# Decode.net
KiCad netlist of a schematic drawn in Altium Designer
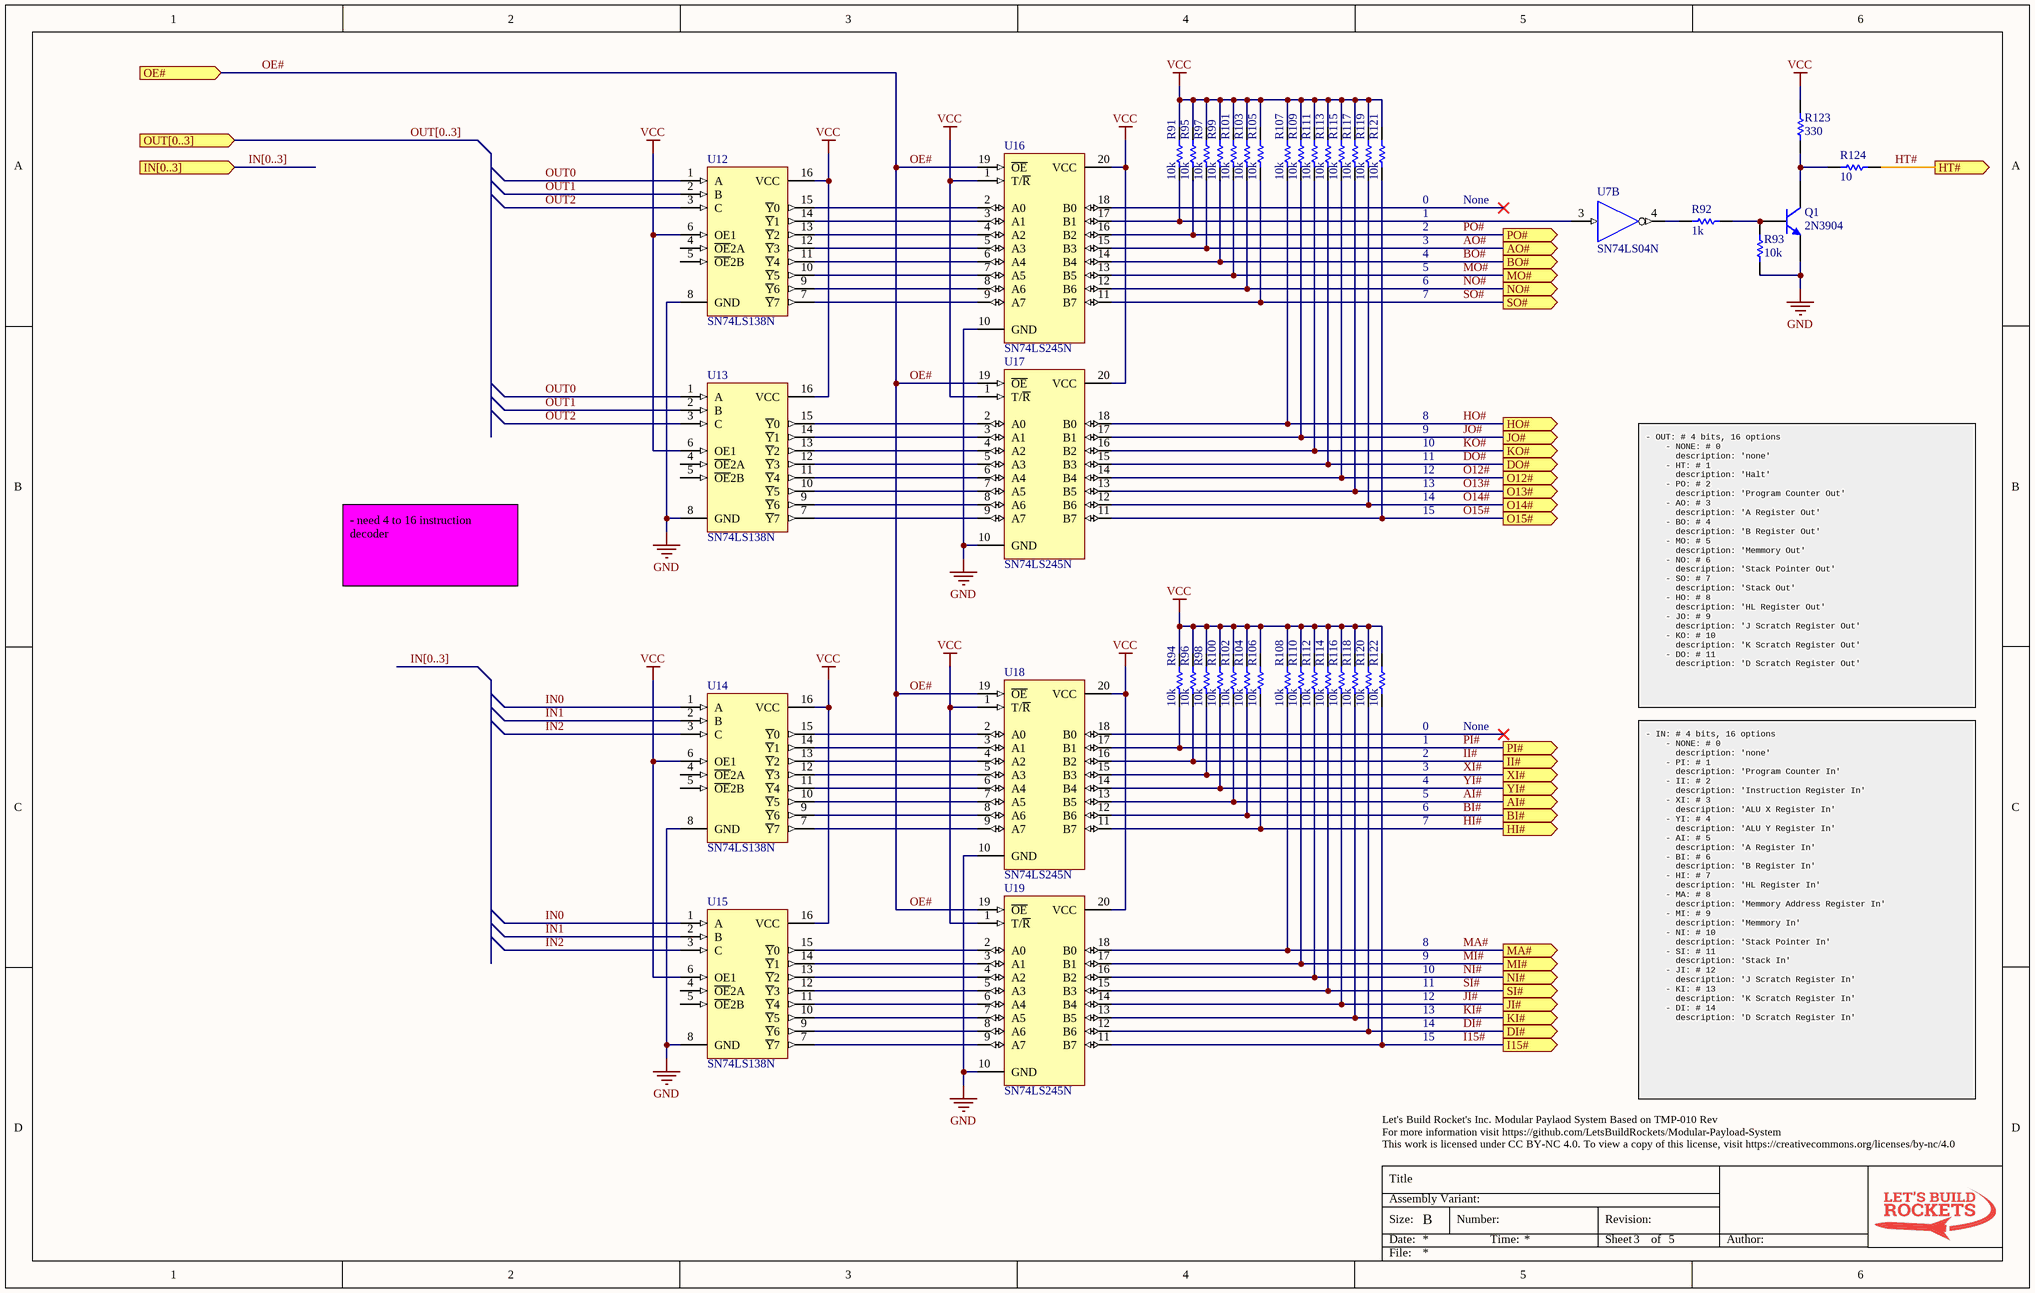
[diagram p0: Decode.SchDoc]

(export (version "E")
  (design (tool "Eeschema 10.0.6"))
  (components
    (comp (ref "Q1")
      (value "2N3904")
      (footprint "TO-92A")
      (description "NPN General Purpose Amplifier")
      (fields (field (name "PUBLISHER") "Altium Limited"))
      (libsource (lib "Miscellaneous Devices") (part "2N3904"))
    )
    (comp (ref "R91")
      (value "10k")
      (footprint "AXIAL-0.3")
      (description "Resistor")
      (fields (field (name "Comment") "Res1") (field (name "PUBLISHER") "Altium Limited"))
      (libsource (lib "Miscellaneous Devices") (part "Res1"))
    )
    (comp (ref "R92")
      (value "1k")
      (footprint "AXIAL-0.3")
      (description "Resistor")
      (fields (field (name "Comment") "Res1") (field (name "PUBLISHER") "Altium Limited"))
      (libsource (lib "Miscellaneous Devices") (part "Res1"))
    )
    (comp (ref "R93")
      (value "10k")
      (footprint "AXIAL-0.3")
      (description "Resistor")
      (fields (field (name "Comment") "Res1") (field (name "PUBLISHER") "Altium Limited"))
      (libsource (lib "Miscellaneous Devices") (part "Res1"))
    )
    (comp (ref "R94")
      (value "10k")
      (footprint "AXIAL-0.3")
      (description "Resistor")
      (fields (field (name "Comment") "Res1") (field (name "PUBLISHER") "Altium Limited"))
      (libsource (lib "Miscellaneous Devices") (part "Res1"))
    )
    (comp (ref "R95")
      (value "10k")
      (footprint "AXIAL-0.3")
      (description "Resistor")
      (fields (field (name "Comment") "Res1") (field (name "PUBLISHER") "Altium Limited"))
      (libsource (lib "Miscellaneous Devices") (part "Res1"))
    )
    (comp (ref "R96")
      (value "10k")
      (footprint "AXIAL-0.3")
      (description "Resistor")
      (fields (field (name "Comment") "Res1") (field (name "PUBLISHER") "Altium Limited"))
      (libsource (lib "Miscellaneous Devices") (part "Res1"))
    )
    (comp (ref "R97")
      (value "10k")
      (footprint "AXIAL-0.3")
      (description "Resistor")
      (fields (field (name "Comment") "Res1") (field (name "PUBLISHER") "Altium Limited"))
      (libsource (lib "Miscellaneous Devices") (part "Res1"))
    )
    (comp (ref "R98")
      (value "10k")
      (footprint "AXIAL-0.3")
      (description "Resistor")
      (fields (field (name "Comment") "Res1") (field (name "PUBLISHER") "Altium Limited"))
      (libsource (lib "Miscellaneous Devices") (part "Res1"))
    )
    (comp (ref "R99")
      (value "10k")
      (footprint "AXIAL-0.3")
      (description "Resistor")
      (fields (field (name "Comment") "Res1") (field (name "PUBLISHER") "Altium Limited"))
      (libsource (lib "Miscellaneous Devices") (part "Res1"))
    )
    (comp (ref "R100")
      (value "10k")
      (footprint "AXIAL-0.3")
      (description "Resistor")
      (fields (field (name "Comment") "Res1") (field (name "PUBLISHER") "Altium Limited"))
      (libsource (lib "Miscellaneous Devices") (part "Res1"))
    )
    (comp (ref "R101")
      (value "10k")
      (footprint "AXIAL-0.3")
      (description "Resistor")
      (fields (field (name "Comment") "Res1") (field (name "PUBLISHER") "Altium Limited"))
      (libsource (lib "Miscellaneous Devices") (part "Res1"))
    )
    (comp (ref "R102")
      (value "10k")
      (footprint "AXIAL-0.3")
      (description "Resistor")
      (fields (field (name "Comment") "Res1") (field (name "PUBLISHER") "Altium Limited"))
      (libsource (lib "Miscellaneous Devices") (part "Res1"))
    )
    (comp (ref "R103")
      (value "10k")
      (footprint "AXIAL-0.3")
      (description "Resistor")
      (fields (field (name "Comment") "Res1") (field (name "PUBLISHER") "Altium Limited"))
      (libsource (lib "Miscellaneous Devices") (part "Res1"))
    )
    (comp (ref "R104")
      (value "10k")
      (footprint "AXIAL-0.3")
      (description "Resistor")
      (fields (field (name "Comment") "Res1") (field (name "PUBLISHER") "Altium Limited"))
      (libsource (lib "Miscellaneous Devices") (part "Res1"))
    )
    (comp (ref "R105")
      (value "10k")
      (footprint "AXIAL-0.3")
      (description "Resistor")
      (fields (field (name "Comment") "Res1") (field (name "PUBLISHER") "Altium Limited"))
      (libsource (lib "Miscellaneous Devices") (part "Res1"))
    )
    (comp (ref "R106")
      (value "10k")
      (footprint "AXIAL-0.3")
      (description "Resistor")
      (fields (field (name "Comment") "Res1") (field (name "PUBLISHER") "Altium Limited"))
      (libsource (lib "Miscellaneous Devices") (part "Res1"))
    )
    (comp (ref "R107")
      (value "10k")
      (footprint "AXIAL-0.3")
      (description "Resistor")
      (fields (field (name "Comment") "Res1") (field (name "PUBLISHER") "Altium Limited"))
      (libsource (lib "Miscellaneous Devices") (part "Res1"))
    )
    (comp (ref "R108")
      (value "10k")
      (footprint "AXIAL-0.3")
      (description "Resistor")
      (fields (field (name "Comment") "Res1") (field (name "PUBLISHER") "Altium Limited"))
      (libsource (lib "Miscellaneous Devices") (part "Res1"))
    )
    (comp (ref "R109")
      (value "10k")
      (footprint "AXIAL-0.3")
      (description "Resistor")
      (fields (field (name "Comment") "Res1") (field (name "PUBLISHER") "Altium Limited"))
      (libsource (lib "Miscellaneous Devices") (part "Res1"))
    )
    (comp (ref "R110")
      (value "10k")
      (footprint "AXIAL-0.3")
      (description "Resistor")
      (fields (field (name "Comment") "Res1") (field (name "PUBLISHER") "Altium Limited"))
      (libsource (lib "Miscellaneous Devices") (part "Res1"))
    )
    (comp (ref "R111")
      (value "10k")
      (footprint "AXIAL-0.3")
      (description "Resistor")
      (fields (field (name "Comment") "Res1") (field (name "PUBLISHER") "Altium Limited"))
      (libsource (lib "Miscellaneous Devices") (part "Res1"))
    )
    (comp (ref "R112")
      (value "10k")
      (footprint "AXIAL-0.3")
      (description "Resistor")
      (fields (field (name "Comment") "Res1") (field (name "PUBLISHER") "Altium Limited"))
      (libsource (lib "Miscellaneous Devices") (part "Res1"))
    )
    (comp (ref "R113")
      (value "10k")
      (footprint "AXIAL-0.3")
      (description "Resistor")
      (fields (field (name "Comment") "Res1") (field (name "PUBLISHER") "Altium Limited"))
      (libsource (lib "Miscellaneous Devices") (part "Res1"))
    )
    (comp (ref "R114")
      (value "10k")
      (footprint "AXIAL-0.3")
      (description "Resistor")
      (fields (field (name "Comment") "Res1") (field (name "PUBLISHER") "Altium Limited"))
      (libsource (lib "Miscellaneous Devices") (part "Res1"))
    )
    (comp (ref "R115")
      (value "10k")
      (footprint "AXIAL-0.3")
      (description "Resistor")
      (fields (field (name "Comment") "Res1") (field (name "PUBLISHER") "Altium Limited"))
      (libsource (lib "Miscellaneous Devices") (part "Res1"))
    )
    (comp (ref "R116")
      (value "10k")
      (footprint "AXIAL-0.3")
      (description "Resistor")
      (fields (field (name "Comment") "Res1") (field (name "PUBLISHER") "Altium Limited"))
      (libsource (lib "Miscellaneous Devices") (part "Res1"))
    )
    (comp (ref "R117")
      (value "10k")
      (footprint "AXIAL-0.3")
      (description "Resistor")
      (fields (field (name "Comment") "Res1") (field (name "PUBLISHER") "Altium Limited"))
      (libsource (lib "Miscellaneous Devices") (part "Res1"))
    )
    (comp (ref "R118")
      (value "10k")
      (footprint "AXIAL-0.3")
      (description "Resistor")
      (fields (field (name "Comment") "Res1") (field (name "PUBLISHER") "Altium Limited"))
      (libsource (lib "Miscellaneous Devices") (part "Res1"))
    )
    (comp (ref "R119")
      (value "10k")
      (footprint "AXIAL-0.3")
      (description "Resistor")
      (fields (field (name "Comment") "Res1") (field (name "PUBLISHER") "Altium Limited"))
      (libsource (lib "Miscellaneous Devices") (part "Res1"))
    )
    (comp (ref "R120")
      (value "10k")
      (footprint "AXIAL-0.3")
      (description "Resistor")
      (fields (field (name "Comment") "Res1") (field (name "PUBLISHER") "Altium Limited"))
      (libsource (lib "Miscellaneous Devices") (part "Res1"))
    )
    (comp (ref "R121")
      (value "10k")
      (footprint "AXIAL-0.3")
      (description "Resistor")
      (fields (field (name "Comment") "Res1") (field (name "PUBLISHER") "Altium Limited"))
      (libsource (lib "Miscellaneous Devices") (part "Res1"))
    )
    (comp (ref "R122")
      (value "10k")
      (footprint "AXIAL-0.3")
      (description "Resistor")
      (fields (field (name "Comment") "Res1") (field (name "PUBLISHER") "Altium Limited"))
      (libsource (lib "Miscellaneous Devices") (part "Res1"))
    )
    (comp (ref "R123")
      (value "330")
      (footprint "AXIAL-0.3")
      (description "Resistor")
      (fields (field (name "Comment") "Res1") (field (name "PUBLISHER") "Altium Limited"))
      (libsource (lib "Miscellaneous Devices") (part "Res1"))
    )
    (comp (ref "R124")
      (value "10")
      (footprint "AXIAL-0.3")
      (description "Resistor")
      (fields (field (name "Comment") "Res1") (field (name "PUBLISHER") "Altium Limited"))
      (libsource (lib "Miscellaneous Devices") (part "Res1"))
    )
    (comp (ref "U7")
      (value "SN74LS04N")
      (footprint "N014")
      (description "Hex Inverter")
      (fields (field (name "PUBLISHER") "Altium Limited"))
      (libsource (lib "TI Logic Gate 2") (part "SN74LS04N"))
    )
    (comp (ref "U12")
      (value "SN74LS138N")
      (footprint "N016")
      (description "3-Line to 8-Line Decoder / Demultiplexer")
      (fields (field (name "PUBLISHER") "Altium Limited"))
      (libsource (lib "TI Logic Decoder Demux") (part "SN74LS138N"))
    )
    (comp (ref "U13")
      (value "SN74LS138N")
      (footprint "N016")
      (description "3-Line to 8-Line Decoder / Demultiplexer")
      (fields (field (name "PUBLISHER") "Altium Limited"))
      (libsource (lib "TI Logic Decoder Demux") (part "SN74LS138N"))
    )
    (comp (ref "U14")
      (value "SN74LS138N")
      (footprint "N016")
      (description "3-Line to 8-Line Decoder / Demultiplexer")
      (fields (field (name "PUBLISHER") "Altium Limited"))
      (libsource (lib "TI Logic Decoder Demux") (part "SN74LS138N"))
    )
    (comp (ref "U15")
      (value "SN74LS138N")
      (footprint "N016")
      (description "3-Line to 8-Line Decoder / Demultiplexer")
      (fields (field (name "PUBLISHER") "Altium Limited"))
      (libsource (lib "TI Logic Decoder Demux") (part "SN74LS138N"))
    )
    (comp (ref "U16")
      (value "SN74LS245N")
      (footprint "N020")
      (description "Octal Bus Transceiver with 3-State Outputs")
      (fields (field (name "PUBLISHER") "Altium Limited"))
      (libsource (lib "TI Interface 8-Bit Line Transceiver") (part "SN74LS245N"))
    )
    (comp (ref "U17")
      (value "SN74LS245N")
      (footprint "N020")
      (description "Octal Bus Transceiver with 3-State Outputs")
      (fields (field (name "PUBLISHER") "Altium Limited"))
      (libsource (lib "TI Interface 8-Bit Line Transceiver") (part "SN74LS245N"))
    )
    (comp (ref "U18")
      (value "SN74LS245N")
      (footprint "N020")
      (description "Octal Bus Transceiver with 3-State Outputs")
      (fields (field (name "PUBLISHER") "Altium Limited"))
      (libsource (lib "TI Interface 8-Bit Line Transceiver") (part "SN74LS245N"))
    )
    (comp (ref "U19")
      (value "SN74LS245N")
      (footprint "N020")
      (description "Octal Bus Transceiver with 3-State Outputs")
      (fields (field (name "PUBLISHER") "Altium Limited"))
      (libsource (lib "TI Interface 8-Bit Line Transceiver") (part "SN74LS245N"))
    )
  )
  (nets
    (net (code "3") (name "/AI#") (class "Default")
      (node (ref "R102") (pin "1") (pinfunction "1_1") (pintype "passive"))
      (node (ref "U18") (pin "13") (pinfunction "B5_13") (pintype "bidirectional"))
    )
    (net (code "4") (name "/AO#") (class "Default")
      (node (ref "R97") (pin "1") (pinfunction "1_1") (pintype "passive"))
      (node (ref "U16") (pin "15") (pinfunction "B3_15") (pintype "bidirectional"))
    )
    (net (code "5") (name "/BI#") (class "Default")
      (node (ref "R104") (pin "1") (pinfunction "1_1") (pintype "passive"))
      (node (ref "U18") (pin "12") (pinfunction "B6_12") (pintype "bidirectional"))
    )
    (net (code "6") (name "/BO#") (class "Default")
      (node (ref "R99") (pin "1") (pinfunction "1_1") (pintype "passive"))
      (node (ref "U16") (pin "14") (pinfunction "B4_14") (pintype "bidirectional"))
    )
    (net (code "7") (name "/DI#") (class "Default")
      (node (ref "R120") (pin "1") (pinfunction "1_1") (pintype "passive"))
      (node (ref "U19") (pin "12") (pinfunction "B6_12") (pintype "bidirectional"))
    )
    (net (code "8") (name "/DO#") (class "Default")
      (node (ref "R113") (pin "1") (pinfunction "1_1") (pintype "passive"))
      (node (ref "U17") (pin "15") (pinfunction "B3_15") (pintype "bidirectional"))
    )
    (net (code "9") (name "/HI#") (class "Default")
      (node (ref "R106") (pin "1") (pinfunction "1_1") (pintype "passive"))
      (node (ref "U18") (pin "11") (pinfunction "B7_11") (pintype "bidirectional"))
    )
    (net (code "10") (name "/HO#") (class "Default")
      (node (ref "R107") (pin "1") (pinfunction "1_1") (pintype "passive"))
      (node (ref "U17") (pin "18") (pinfunction "B0_18") (pintype "bidirectional"))
    )
    (net (code "11") (name "/HT#") (class "Default")
      (node (ref "R124") (pin "1") (pinfunction "1_1") (pintype "passive"))
    )
    (net (code "12") (name "/I15#") (class "Default")
      (node (ref "R122") (pin "1") (pinfunction "1_1") (pintype "passive"))
      (node (ref "U19") (pin "11") (pinfunction "B7_11") (pintype "bidirectional"))
    )
    (net (code "13") (name "/II#") (class "Default")
      (node (ref "R96") (pin "1") (pinfunction "1_1") (pintype "passive"))
      (node (ref "U18") (pin "16") (pinfunction "B2_16") (pintype "bidirectional"))
    )
    (net (code "14") (name "/IN0") (class "Default")
      (node (ref "U14") (pin "1") (pinfunction "A_1") (pintype "input"))
      (node (ref "U15") (pin "1") (pinfunction "A_1") (pintype "input"))
    )
    (net (code "15") (name "/IN1") (class "Default")
      (node (ref "U14") (pin "2") (pinfunction "B_2") (pintype "input"))
      (node (ref "U15") (pin "2") (pinfunction "B_2") (pintype "input"))
    )
    (net (code "16") (name "/IN2") (class "Default")
      (node (ref "U14") (pin "3") (pinfunction "C_3") (pintype "input"))
      (node (ref "U15") (pin "3") (pinfunction "C_3") (pintype "input"))
    )
    (net (code "18") (name "/JI#") (class "Default")
      (node (ref "R116") (pin "1") (pinfunction "1_1") (pintype "passive"))
      (node (ref "U19") (pin "14") (pinfunction "B4_14") (pintype "bidirectional"))
    )
    (net (code "19") (name "/JO#") (class "Default")
      (node (ref "R109") (pin "1") (pinfunction "1_1") (pintype "passive"))
      (node (ref "U17") (pin "17") (pinfunction "B1_17") (pintype "bidirectional"))
    )
    (net (code "20") (name "/KI#") (class "Default")
      (node (ref "R118") (pin "1") (pinfunction "1_1") (pintype "passive"))
      (node (ref "U19") (pin "13") (pinfunction "B5_13") (pintype "bidirectional"))
    )
    (net (code "21") (name "/KO#") (class "Default")
      (node (ref "R111") (pin "1") (pinfunction "1_1") (pintype "passive"))
      (node (ref "U17") (pin "16") (pinfunction "B2_16") (pintype "bidirectional"))
    )
    (net (code "22") (name "/MA#") (class "Default")
      (node (ref "R108") (pin "1") (pinfunction "1_1") (pintype "passive"))
      (node (ref "U19") (pin "18") (pinfunction "B0_18") (pintype "bidirectional"))
    )
    (net (code "23") (name "/MI#") (class "Default")
      (node (ref "R110") (pin "1") (pinfunction "1_1") (pintype "passive"))
      (node (ref "U19") (pin "17") (pinfunction "B1_17") (pintype "bidirectional"))
    )
    (net (code "24") (name "/MO#") (class "Default")
      (node (ref "R101") (pin "1") (pinfunction "1_1") (pintype "passive"))
      (node (ref "U16") (pin "13") (pinfunction "B5_13") (pintype "bidirectional"))
    )
    (net (code "25") (name "/NI#") (class "Default")
      (node (ref "R112") (pin "1") (pinfunction "1_1") (pintype "passive"))
      (node (ref "U19") (pin "16") (pinfunction "B2_16") (pintype "bidirectional"))
    )
    (net (code "26") (name "/NO#") (class "Default")
      (node (ref "R103") (pin "1") (pinfunction "1_1") (pintype "passive"))
      (node (ref "U16") (pin "12") (pinfunction "B6_12") (pintype "bidirectional"))
    )
    (net (code "27") (name "/O12#") (class "Default")
      (node (ref "R115") (pin "1") (pinfunction "1_1") (pintype "passive"))
      (node (ref "U17") (pin "14") (pinfunction "B4_14") (pintype "bidirectional"))
    )
    (net (code "28") (name "/O13#") (class "Default")
      (node (ref "R117") (pin "1") (pinfunction "1_1") (pintype "passive"))
      (node (ref "U17") (pin "13") (pinfunction "B5_13") (pintype "bidirectional"))
    )
    (net (code "29") (name "/O14#") (class "Default")
      (node (ref "R119") (pin "1") (pinfunction "1_1") (pintype "passive"))
      (node (ref "U17") (pin "12") (pinfunction "B6_12") (pintype "bidirectional"))
    )
    (net (code "30") (name "/O15#") (class "Default")
      (node (ref "R121") (pin "1") (pinfunction "1_1") (pintype "passive"))
      (node (ref "U17") (pin "11") (pinfunction "B7_11") (pintype "bidirectional"))
    )
    (net (code "31") (name "/OE#") (class "Default")
      (node (ref "U16") (pin "19") (pinfunction "~{OE}_19") (pintype "input"))
      (node (ref "U17") (pin "19") (pinfunction "~{OE}_19") (pintype "input"))
      (node (ref "U18") (pin "19") (pinfunction "~{OE}_19") (pintype "input"))
      (node (ref "U19") (pin "19") (pinfunction "~{OE}_19") (pintype "input"))
    )
    (net (code "32") (name "/OUT0") (class "Default")
      (node (ref "U12") (pin "1") (pinfunction "A_1") (pintype "input"))
      (node (ref "U13") (pin "1") (pinfunction "A_1") (pintype "input"))
    )
    (net (code "33") (name "/OUT1") (class "Default")
      (node (ref "U12") (pin "2") (pinfunction "B_2") (pintype "input"))
      (node (ref "U13") (pin "2") (pinfunction "B_2") (pintype "input"))
    )
    (net (code "34") (name "/OUT2") (class "Default")
      (node (ref "U12") (pin "3") (pinfunction "C_3") (pintype "input"))
      (node (ref "U13") (pin "3") (pinfunction "C_3") (pintype "input"))
    )
    (net (code "36") (name "/PI#") (class "Default")
      (node (ref "R94") (pin "1") (pinfunction "1_1") (pintype "passive"))
      (node (ref "U18") (pin "17") (pinfunction "B1_17") (pintype "bidirectional"))
    )
    (net (code "37") (name "/PO#") (class "Default")
      (node (ref "R95") (pin "1") (pinfunction "1_1") (pintype "passive"))
      (node (ref "U16") (pin "16") (pinfunction "B2_16") (pintype "bidirectional"))
    )
    (net (code "38") (name "/SI#") (class "Default")
      (node (ref "R114") (pin "1") (pinfunction "1_1") (pintype "passive"))
      (node (ref "U19") (pin "15") (pinfunction "B3_15") (pintype "bidirectional"))
    )
    (net (code "39") (name "/SO#") (class "Default")
      (node (ref "R105") (pin "1") (pinfunction "1_1") (pintype "passive"))
      (node (ref "U16") (pin "11") (pinfunction "B7_11") (pintype "bidirectional"))
    )
    (net (code "40") (name "/XI#") (class "Default")
      (node (ref "R98") (pin "1") (pinfunction "1_1") (pintype "passive"))
      (node (ref "U18") (pin "15") (pinfunction "B3_15") (pintype "bidirectional"))
    )
    (net (code "41") (name "/YI#") (class "Default")
      (node (ref "R100") (pin "1") (pinfunction "1_1") (pintype "passive"))
      (node (ref "U18") (pin "14") (pinfunction "B4_14") (pintype "bidirectional"))
    )
    (net (code "42") (name "GND") (class "Default")
      (node (ref "Q1") (pin "1") (pinfunction "E_1") (pintype "passive"))
      (node (ref "R93") (pin "2") (pinfunction "2_2") (pintype "passive"))
      (node (ref "U12") (pin "8") (pinfunction "GND_8") (pintype "power_in"))
      (node (ref "U13") (pin "8") (pinfunction "GND_8") (pintype "power_in"))
      (node (ref "U14") (pin "8") (pinfunction "GND_8") (pintype "power_in"))
      (node (ref "U15") (pin "8") (pinfunction "GND_8") (pintype "power_in"))
      (node (ref "U16") (pin "10") (pinfunction "GND_10") (pintype "power_in"))
      (node (ref "U17") (pin "10") (pinfunction "GND_10") (pintype "power_in"))
      (node (ref "U18") (pin "10") (pinfunction "GND_10") (pintype "power_in"))
      (node (ref "U19") (pin "10") (pinfunction "GND_10") (pintype "power_in"))
      (node (ref "U7") (pin "7") (pinfunction "GND_7") (pintype "power_in"))
    )
    (net (code "43") (name "Net-(Q1-B)") (class "Default")
      (node (ref "Q1") (pin "2") (pinfunction "B_2") (pintype "passive"))
      (node (ref "R92") (pin "1") (pinfunction "1_1") (pintype "passive"))
      (node (ref "R93") (pin "1") (pinfunction "1_1") (pintype "passive"))
    )
    (net (code "44") (name "Net-(Q1-C)") (class "Default")
      (node (ref "Q1") (pin "3") (pinfunction "C_3") (pintype "passive"))
      (node (ref "R123") (pin "2") (pinfunction "2_2") (pintype "passive"))
      (node (ref "R124") (pin "2") (pinfunction "2_2") (pintype "passive"))
    )
    (net (code "45") (name "Net-(U7B-Y)") (class "Default")
      (node (ref "R92") (pin "2") (pinfunction "2_2") (pintype "passive"))
      (node (ref "U7") (pin "4") (pinfunction "Y_4") (pintype "output"))
    )
    (net (code "46") (name "Net-(U12-~{Y}0)") (class "Default")
      (node (ref "U12") (pin "15") (pinfunction "~{Y}0_15") (pintype "output"))
      (node (ref "U16") (pin "2") (pinfunction "A0_2") (pintype "bidirectional"))
    )
    (net (code "47") (name "Net-(U12-~{Y}1)") (class "Default")
      (node (ref "U12") (pin "14") (pinfunction "~{Y}1_14") (pintype "output"))
      (node (ref "U16") (pin "3") (pinfunction "A1_3") (pintype "bidirectional"))
    )
    (net (code "48") (name "Net-(U12-~{Y}2)") (class "Default")
      (node (ref "U12") (pin "13") (pinfunction "~{Y}2_13") (pintype "output"))
      (node (ref "U16") (pin "4") (pinfunction "A2_4") (pintype "bidirectional"))
    )
    (net (code "49") (name "Net-(U12-~{Y}3)") (class "Default")
      (node (ref "U12") (pin "12") (pinfunction "~{Y}3_12") (pintype "output"))
      (node (ref "U16") (pin "5") (pinfunction "A3_5") (pintype "bidirectional"))
    )
    (net (code "50") (name "Net-(U12-~{Y}4)") (class "Default")
      (node (ref "U12") (pin "11") (pinfunction "~{Y}4_11") (pintype "output"))
      (node (ref "U16") (pin "6") (pinfunction "A4_6") (pintype "bidirectional"))
    )
    (net (code "51") (name "Net-(U12-~{Y}5)") (class "Default")
      (node (ref "U12") (pin "10") (pinfunction "~{Y}5_10") (pintype "output"))
      (node (ref "U16") (pin "7") (pinfunction "A5_7") (pintype "bidirectional"))
    )
    (net (code "52") (name "Net-(U12-~{Y}6)") (class "Default")
      (node (ref "U12") (pin "9") (pinfunction "~{Y}6_9") (pintype "output"))
      (node (ref "U16") (pin "8") (pinfunction "A6_8") (pintype "bidirectional"))
    )
    (net (code "53") (name "Net-(U12-~{Y}7)") (class "Default")
      (node (ref "U12") (pin "7") (pinfunction "~{Y}7_7") (pintype "output"))
      (node (ref "U16") (pin "9") (pinfunction "A7_9") (pintype "bidirectional"))
    )
    (net (code "54") (name "Net-(U13-~{Y}0)") (class "Default")
      (node (ref "U13") (pin "15") (pinfunction "~{Y}0_15") (pintype "output"))
      (node (ref "U17") (pin "2") (pinfunction "A0_2") (pintype "bidirectional"))
    )
    (net (code "55") (name "Net-(U13-~{Y}1)") (class "Default")
      (node (ref "U13") (pin "14") (pinfunction "~{Y}1_14") (pintype "output"))
      (node (ref "U17") (pin "3") (pinfunction "A1_3") (pintype "bidirectional"))
    )
    (net (code "56") (name "Net-(U13-~{Y}2)") (class "Default")
      (node (ref "U13") (pin "13") (pinfunction "~{Y}2_13") (pintype "output"))
      (node (ref "U17") (pin "4") (pinfunction "A2_4") (pintype "bidirectional"))
    )
    (net (code "57") (name "Net-(U13-~{Y}3)") (class "Default")
      (node (ref "U13") (pin "12") (pinfunction "~{Y}3_12") (pintype "output"))
      (node (ref "U17") (pin "5") (pinfunction "A3_5") (pintype "bidirectional"))
    )
    (net (code "58") (name "Net-(U13-~{Y}4)") (class "Default")
      (node (ref "U13") (pin "11") (pinfunction "~{Y}4_11") (pintype "output"))
      (node (ref "U17") (pin "6") (pinfunction "A4_6") (pintype "bidirectional"))
    )
    (net (code "59") (name "Net-(U13-~{Y}5)") (class "Default")
      (node (ref "U13") (pin "10") (pinfunction "~{Y}5_10") (pintype "output"))
      (node (ref "U17") (pin "7") (pinfunction "A5_7") (pintype "bidirectional"))
    )
    (net (code "60") (name "Net-(U13-~{Y}6)") (class "Default")
      (node (ref "U13") (pin "9") (pinfunction "~{Y}6_9") (pintype "output"))
      (node (ref "U17") (pin "8") (pinfunction "A6_8") (pintype "bidirectional"))
    )
    (net (code "61") (name "Net-(U13-~{Y}7)") (class "Default")
      (node (ref "U13") (pin "7") (pinfunction "~{Y}7_7") (pintype "output"))
      (node (ref "U17") (pin "9") (pinfunction "A7_9") (pintype "bidirectional"))
    )
    (net (code "62") (name "Net-(U14-~{Y}0)") (class "Default")
      (node (ref "U14") (pin "15") (pinfunction "~{Y}0_15") (pintype "output"))
      (node (ref "U18") (pin "2") (pinfunction "A0_2") (pintype "bidirectional"))
    )
    (net (code "63") (name "Net-(U14-~{Y}1)") (class "Default")
      (node (ref "U14") (pin "14") (pinfunction "~{Y}1_14") (pintype "output"))
      (node (ref "U18") (pin "3") (pinfunction "A1_3") (pintype "bidirectional"))
    )
    (net (code "64") (name "Net-(U14-~{Y}2)") (class "Default")
      (node (ref "U14") (pin "13") (pinfunction "~{Y}2_13") (pintype "output"))
      (node (ref "U18") (pin "4") (pinfunction "A2_4") (pintype "bidirectional"))
    )
    (net (code "65") (name "Net-(U14-~{Y}3)") (class "Default")
      (node (ref "U14") (pin "12") (pinfunction "~{Y}3_12") (pintype "output"))
      (node (ref "U18") (pin "5") (pinfunction "A3_5") (pintype "bidirectional"))
    )
    (net (code "66") (name "Net-(U14-~{Y}4)") (class "Default")
      (node (ref "U14") (pin "11") (pinfunction "~{Y}4_11") (pintype "output"))
      (node (ref "U18") (pin "6") (pinfunction "A4_6") (pintype "bidirectional"))
    )
    (net (code "67") (name "Net-(U14-~{Y}5)") (class "Default")
      (node (ref "U14") (pin "10") (pinfunction "~{Y}5_10") (pintype "output"))
      (node (ref "U18") (pin "7") (pinfunction "A5_7") (pintype "bidirectional"))
    )
    (net (code "68") (name "Net-(U14-~{Y}6)") (class "Default")
      (node (ref "U14") (pin "9") (pinfunction "~{Y}6_9") (pintype "output"))
      (node (ref "U18") (pin "8") (pinfunction "A6_8") (pintype "bidirectional"))
    )
    (net (code "69") (name "Net-(U14-~{Y}7)") (class "Default")
      (node (ref "U14") (pin "7") (pinfunction "~{Y}7_7") (pintype "output"))
      (node (ref "U18") (pin "9") (pinfunction "A7_9") (pintype "bidirectional"))
    )
    (net (code "70") (name "Net-(U15-~{Y}0)") (class "Default")
      (node (ref "U15") (pin "15") (pinfunction "~{Y}0_15") (pintype "output"))
      (node (ref "U19") (pin "2") (pinfunction "A0_2") (pintype "bidirectional"))
    )
    (net (code "71") (name "Net-(U15-~{Y}1)") (class "Default")
      (node (ref "U15") (pin "14") (pinfunction "~{Y}1_14") (pintype "output"))
      (node (ref "U19") (pin "3") (pinfunction "A1_3") (pintype "bidirectional"))
    )
    (net (code "72") (name "Net-(U15-~{Y}2)") (class "Default")
      (node (ref "U15") (pin "13") (pinfunction "~{Y}2_13") (pintype "output"))
      (node (ref "U19") (pin "4") (pinfunction "A2_4") (pintype "bidirectional"))
    )
    (net (code "73") (name "Net-(U15-~{Y}3)") (class "Default")
      (node (ref "U15") (pin "12") (pinfunction "~{Y}3_12") (pintype "output"))
      (node (ref "U19") (pin "5") (pinfunction "A3_5") (pintype "bidirectional"))
    )
    (net (code "74") (name "Net-(U15-~{Y}4)") (class "Default")
      (node (ref "U15") (pin "11") (pinfunction "~{Y}4_11") (pintype "output"))
      (node (ref "U19") (pin "6") (pinfunction "A4_6") (pintype "bidirectional"))
    )
    (net (code "75") (name "Net-(U15-~{Y}5)") (class "Default")
      (node (ref "U15") (pin "10") (pinfunction "~{Y}5_10") (pintype "output"))
      (node (ref "U19") (pin "7") (pinfunction "A5_7") (pintype "bidirectional"))
    )
    (net (code "76") (name "Net-(U15-~{Y}6)") (class "Default")
      (node (ref "U15") (pin "9") (pinfunction "~{Y}6_9") (pintype "output"))
      (node (ref "U19") (pin "8") (pinfunction "A6_8") (pintype "bidirectional"))
    )
    (net (code "77") (name "Net-(U15-~{Y}7)") (class "Default")
      (node (ref "U15") (pin "7") (pinfunction "~{Y}7_7") (pintype "output"))
      (node (ref "U19") (pin "9") (pinfunction "A7_9") (pintype "bidirectional"))
    )
    (net (code "78") (name "Net-(U16-B1)") (class "Default")
      (node (ref "R91") (pin "1") (pinfunction "1_1") (pintype "passive"))
      (node (ref "U16") (pin "17") (pinfunction "B1_17") (pintype "bidirectional"))
      (node (ref "U7") (pin "3") (pinfunction "A_3") (pintype "input"))
    )
    (net (code "79") (name "VCC") (class "Default")
      (node (ref "R100") (pin "2") (pinfunction "2_2") (pintype "passive"))
      (node (ref "R101") (pin "2") (pinfunction "2_2") (pintype "passive"))
      (node (ref "R102") (pin "2") (pinfunction "2_2") (pintype "passive"))
      (node (ref "R103") (pin "2") (pinfunction "2_2") (pintype "passive"))
      (node (ref "R104") (pin "2") (pinfunction "2_2") (pintype "passive"))
      (node (ref "R105") (pin "2") (pinfunction "2_2") (pintype "passive"))
      (node (ref "R106") (pin "2") (pinfunction "2_2") (pintype "passive"))
      (node (ref "R107") (pin "2") (pinfunction "2_2") (pintype "passive"))
      (node (ref "R108") (pin "2") (pinfunction "2_2") (pintype "passive"))
      (node (ref "R109") (pin "2") (pinfunction "2_2") (pintype "passive"))
      (node (ref "R110") (pin "2") (pinfunction "2_2") (pintype "passive"))
      (node (ref "R111") (pin "2") (pinfunction "2_2") (pintype "passive"))
      (node (ref "R112") (pin "2") (pinfunction "2_2") (pintype "passive"))
      (node (ref "R113") (pin "2") (pinfunction "2_2") (pintype "passive"))
      (node (ref "R114") (pin "2") (pinfunction "2_2") (pintype "passive"))
      (node (ref "R115") (pin "2") (pinfunction "2_2") (pintype "passive"))
      (node (ref "R116") (pin "2") (pinfunction "2_2") (pintype "passive"))
      (node (ref "R117") (pin "2") (pinfunction "2_2") (pintype "passive"))
      (node (ref "R118") (pin "2") (pinfunction "2_2") (pintype "passive"))
      (node (ref "R119") (pin "2") (pinfunction "2_2") (pintype "passive"))
      (node (ref "R120") (pin "2") (pinfunction "2_2") (pintype "passive"))
      (node (ref "R121") (pin "2") (pinfunction "2_2") (pintype "passive"))
      (node (ref "R122") (pin "2") (pinfunction "2_2") (pintype "passive"))
      (node (ref "R123") (pin "1") (pinfunction "1_1") (pintype "passive"))
      (node (ref "R91") (pin "2") (pinfunction "2_2") (pintype "passive"))
      (node (ref "R94") (pin "2") (pinfunction "2_2") (pintype "passive"))
      (node (ref "R95") (pin "2") (pinfunction "2_2") (pintype "passive"))
      (node (ref "R96") (pin "2") (pinfunction "2_2") (pintype "passive"))
      (node (ref "R97") (pin "2") (pinfunction "2_2") (pintype "passive"))
      (node (ref "R98") (pin "2") (pinfunction "2_2") (pintype "passive"))
      (node (ref "R99") (pin "2") (pinfunction "2_2") (pintype "passive"))
      (node (ref "U12") (pin "16") (pinfunction "VCC_16") (pintype "power_in"))
      (node (ref "U12") (pin "6") (pinfunction "OE1_6") (pintype "input"))
      (node (ref "U13") (pin "16") (pinfunction "VCC_16") (pintype "power_in"))
      (node (ref "U13") (pin "6") (pinfunction "OE1_6") (pintype "input"))
      (node (ref "U14") (pin "16") (pinfunction "VCC_16") (pintype "power_in"))
      (node (ref "U14") (pin "6") (pinfunction "OE1_6") (pintype "input"))
      (node (ref "U15") (pin "16") (pinfunction "VCC_16") (pintype "power_in"))
      (node (ref "U15") (pin "6") (pinfunction "OE1_6") (pintype "input"))
      (node (ref "U16") (pin "1") (pinfunction "T/~{R}_1") (pintype "input"))
      (node (ref "U16") (pin "20") (pinfunction "VCC_20") (pintype "power_in"))
      (node (ref "U17") (pin "1") (pinfunction "T/~{R}_1") (pintype "input"))
      (node (ref "U17") (pin "20") (pinfunction "VCC_20") (pintype "power_in"))
      (node (ref "U18") (pin "1") (pinfunction "T/~{R}_1") (pintype "input"))
      (node (ref "U18") (pin "20") (pinfunction "VCC_20") (pintype "power_in"))
      (node (ref "U19") (pin "1") (pinfunction "T/~{R}_1") (pintype "input"))
      (node (ref "U19") (pin "20") (pinfunction "VCC_20") (pintype "power_in"))
      (node (ref "U7") (pin "14") (pinfunction "VCC_14") (pintype "power_in"))
    )
    (net (code "80") (name "unconnected-(U12-~{OE}2A-Pad4)") (class "Default")
      (node (ref "U12") (pin "4") (pinfunction "~{OE}2A_4") (pintype "input"))
    )
    (net (code "81") (name "unconnected-(U12-~{OE}2B-Pad5)") (class "Default")
      (node (ref "U12") (pin "5") (pinfunction "~{OE}2B_5") (pintype "input"))
    )
    (net (code "82") (name "unconnected-(U13-~{OE}2A-Pad4)") (class "Default")
      (node (ref "U13") (pin "4") (pinfunction "~{OE}2A_4") (pintype "input"))
    )
    (net (code "83") (name "unconnected-(U13-~{OE}2B-Pad5)") (class "Default")
      (node (ref "U13") (pin "5") (pinfunction "~{OE}2B_5") (pintype "input"))
    )
    (net (code "84") (name "unconnected-(U14-~{OE}2A-Pad4)") (class "Default")
      (node (ref "U14") (pin "4") (pinfunction "~{OE}2A_4") (pintype "input"))
    )
    (net (code "85") (name "unconnected-(U14-~{OE}2B-Pad5)") (class "Default")
      (node (ref "U14") (pin "5") (pinfunction "~{OE}2B_5") (pintype "input"))
    )
    (net (code "86") (name "unconnected-(U15-~{OE}2A-Pad4)") (class "Default")
      (node (ref "U15") (pin "4") (pinfunction "~{OE}2A_4") (pintype "input"))
    )
    (net (code "87") (name "unconnected-(U15-~{OE}2B-Pad5)") (class "Default")
      (node (ref "U15") (pin "5") (pinfunction "~{OE}2B_5") (pintype "input"))
    )
    (net (code "88") (name "unconnected-(U16-B0-Pad18)") (class "Default")
      (node (ref "U16") (pin "18") (pinfunction "B0_18") (pintype "bidirectional+no_connect"))
    )
    (net (code "89") (name "unconnected-(U18-B0-Pad18)") (class "Default")
      (node (ref "U18") (pin "18") (pinfunction "B0_18") (pintype "bidirectional+no_connect"))
    )
  )
)
